# wk.net
KiCad netlist of a schematic drawn in Altium Designer
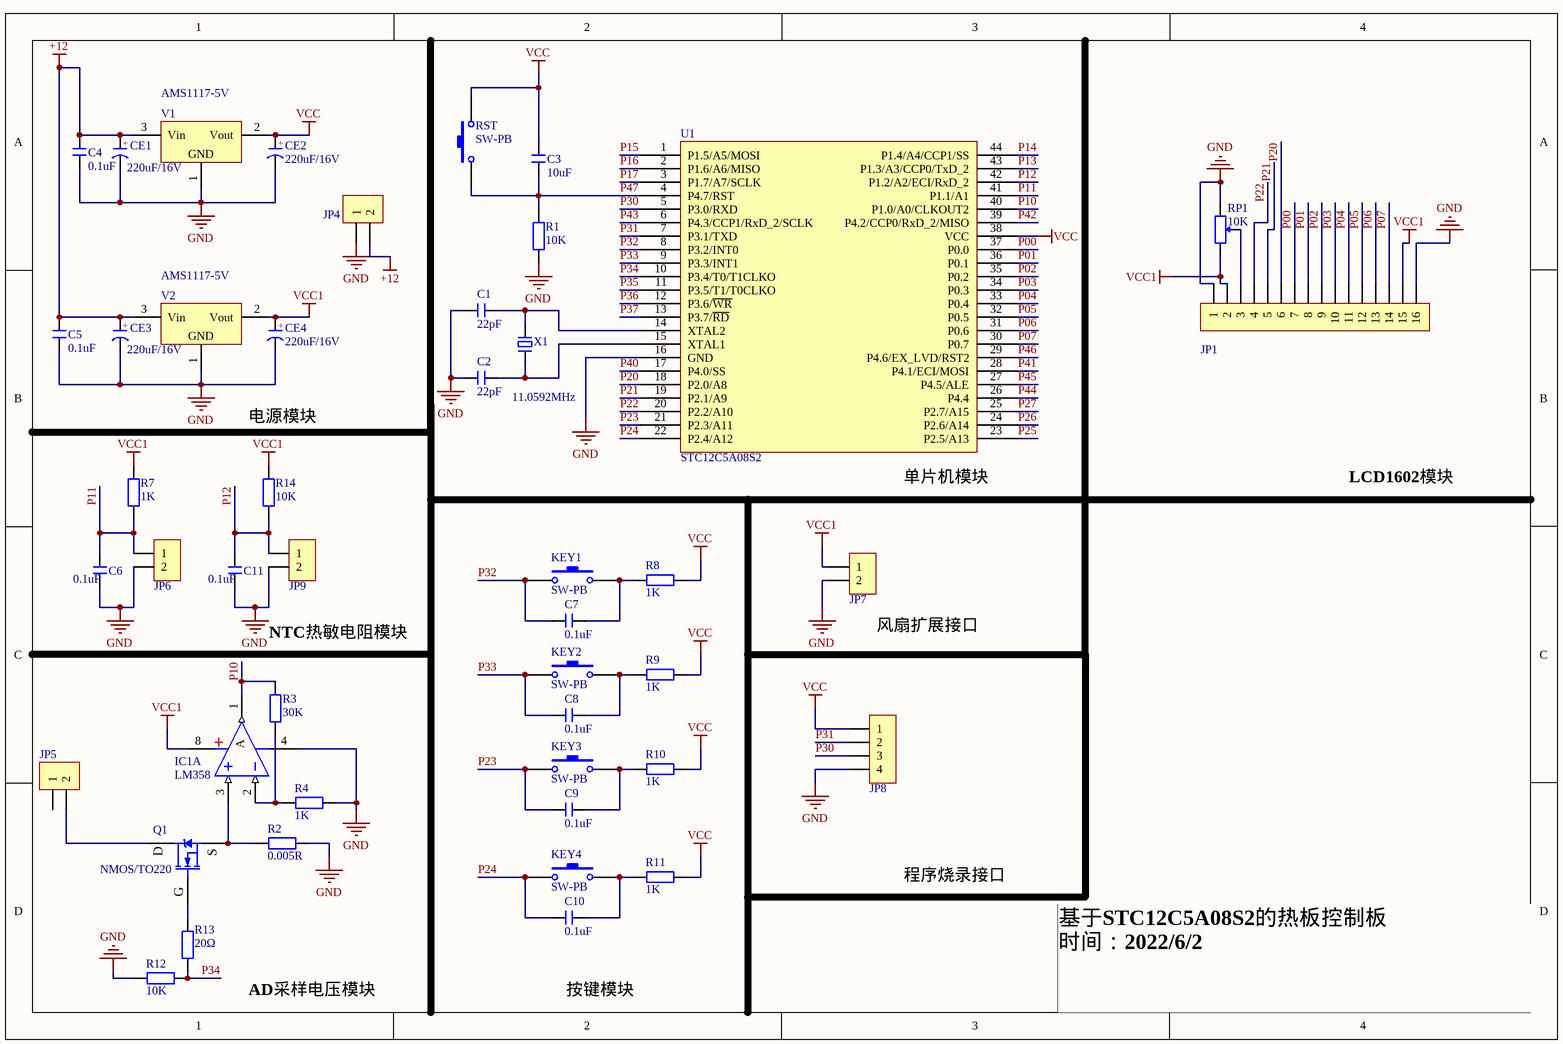
[diagram p0: wk.SchDoc]

(export (version "E")
  (design (tool "Eeschema 10.0.6"))
  (components
    (comp (ref "C1")
      (value "22pF")
      (footprint "C 0805_M")
      (description "贴片电容")
      (libsource (lib "0.1 - 电阻-电容-电感") (part "C"))
    )
    (comp (ref "C2")
      (value "22pF")
      (footprint "C 0805_M")
      (description "贴片电容")
      (libsource (lib "0.1 - 电阻-电容-电感") (part "C"))
    )
    (comp (ref "C3")
      (value "10uF")
      (footprint "C 0805_M")
      (description "贴片电容")
      (libsource (lib "0.1 - 电阻-电容-电感") (part "C"))
    )
    (comp (ref "C4")
      (value "0.1uF")
      (footprint "C 0805_M")
      (description "贴片电容")
      (libsource (lib "0.1 - 电阻-电容-电感") (part "C"))
    )
    (comp (ref "C5")
      (value "0.1uF")
      (footprint "C 0805_M")
      (description "贴片电容")
      (libsource (lib "0.1 - 电阻-电容-电感") (part "C"))
    )
    (comp (ref "C6")
      (value "0.1uF")
      (footprint "C 0805_M")
      (description "贴片电容")
      (libsource (lib "0.1 - 电阻-电容-电感") (part "C"))
    )
    (comp (ref "C7")
      (value "0.1uF")
      (footprint "C 0805_M")
      (description "贴片电容")
      (libsource (lib "0.1 - 电阻-电容-电感") (part "C"))
    )
    (comp (ref "C8")
      (value "0.1uF")
      (footprint "C 0805_M")
      (description "贴片电容")
      (libsource (lib "0.1 - 电阻-电容-电感") (part "C"))
    )
    (comp (ref "C9")
      (value "0.1uF")
      (footprint "C 0805_M")
      (description "贴片电容")
      (libsource (lib "0.1 - 电阻-电容-电感") (part "C"))
    )
    (comp (ref "C10")
      (value "0.1uF")
      (footprint "C 0805_M")
      (description "贴片电容")
      (libsource (lib "0.1 - 电阻-电容-电感") (part "C"))
    )
    (comp (ref "C11")
      (value "0.1uF")
      (footprint "C 0805_M")
      (description "贴片电容")
      (libsource (lib "0.1 - 电阻-电容-电感") (part "C"))
    )
    (comp (ref "CE1")
      (value "220uF/16V")
      (footprint "CAP 2.5*6.3*7")
      (description "直插电解电容")
      (libsource (lib "0.1 - 电阻-电容-电感") (part "CE"))
    )
    (comp (ref "CE2")
      (value "220uF/16V")
      (footprint "CAP 2.5*6.3*7")
      (description "直插电解电容")
      (libsource (lib "0.1 - 电阻-电容-电感") (part "CE"))
    )
    (comp (ref "CE3")
      (value "220uF/16V")
      (footprint "CAP 2.5*6.3*7")
      (description "直插电解电容")
      (libsource (lib "0.1 - 电阻-电容-电感") (part "CE"))
    )
    (comp (ref "CE4")
      (value "220uF/16V")
      (footprint "CAP 2.5*6.3*7")
      (description "直插电解电容")
      (libsource (lib "0.1 - 电阻-电容-电感") (part "CE"))
    )
    (comp (ref "IC1")
      (value "LM358")
      (footprint "DIP8-300")
      (description "双路运放")
      (fields (field (name "版权归属") "源创客"))
      (libsource (lib "1.0 - 常见芯片") (part "LM358"))
    )
    (comp (ref "JP1")
      (value "HDR-1X16")
      (footprint "HDR2.54-LI-16P")
      (description "16P接插件")
      (fields (field (name "版权归属") "源创客"))
      (libsource (lib "4.5   - 接插件-脚距2.54") (part "Header 16"))
    )
    (comp (ref "JP4")
      (value "HDR-1X2")
      (footprint "KF2EDGK5.08-LI-2P")
      (description "2P接插件")
      (fields (field (name "版权归属") "源创客"))
      (libsource (lib "4.10 - 接插件-脚距5.08") (part "Header 2"))
    )
    (comp (ref "JP5")
      (value "HDR-1X2")
      (footprint "KF2EDGK5.08-LI-2P")
      (description "2P接插件")
      (fields (field (name "版权归属") "源创客"))
      (libsource (lib "4.10 - 接插件-脚距5.08") (part "Header 2"))
    )
    (comp (ref "JP6")
      (value "HDR-1X2")
      (footprint "HDR2.54-LI-2P")
      (description "2P接插件")
      (fields (field (name "版权归属") "封装库来自淘宝 ID：黄晶宝石"))
      (libsource (lib "5.4 - 接插件-脚距2.54 (100mil) ") (part "Header 2"))
    )
    (comp (ref "JP7")
      (value "HDR-1X2")
      (footprint "HDR2.54-LI-2P")
      (description "2P接插件")
      (fields (field (name "版权归属") "封装库来自淘宝 ID：黄晶宝石"))
      (libsource (lib "5.4 - 接插件-脚距2.54 (100mil) ") (part "Header 2"))
    )
    (comp (ref "JP8")
      (value "HDR-1X4")
      (footprint "HDR2.54-LI-4P")
      (description "4P接插件")
      (fields (field (name "版权归属") "封装库来自淘宝 ID：黄晶宝石"))
      (libsource (lib "5.4 - 接插件-脚距2.54 (100mil) ") (part "Header 4"))
    )
    (comp (ref "JP9")
      (value "HDR-1X2")
      (footprint "HDR2.54-LI-2P")
      (description "2P接插件")
      (fields (field (name "版权归属") "封装库来自淘宝 ID：黄晶宝石"))
      (libsource (lib "5.4 - 接插件-脚距2.54 (100mil) ") (part "Header 2"))
    )
    (comp (ref "KEY1")
      (value "SW-PB")
      (footprint "SW_PB2_A1")
      (description "微动开关")
      (fields (field (name "PUBLISHER") "Altium Limited"))
      (libsource (lib "0.7 - 常用按键-开关") (part "SW-PB"))
    )
    (comp (ref "KEY2")
      (value "SW-PB")
      (footprint "SW_PB2_A1")
      (description "微动开关")
      (fields (field (name "PUBLISHER") "Altium Limited"))
      (libsource (lib "0.7 - 常用按键-开关") (part "SW-PB"))
    )
    (comp (ref "KEY3")
      (value "SW-PB")
      (footprint "SW_PB2_A1")
      (description "微动开关")
      (fields (field (name "PUBLISHER") "Altium Limited"))
      (libsource (lib "0.7 - 常用按键-开关") (part "SW-PB"))
    )
    (comp (ref "KEY4")
      (value "SW-PB")
      (footprint "SW_PB2_A1")
      (description "微动开关")
      (fields (field (name "PUBLISHER") "Altium Limited"))
      (libsource (lib "0.7 - 常用按键-开关") (part "SW-PB"))
    )
    (comp (ref "Q1")
      (value "NMOS/TO220")
      (footprint "TO220A")
      (description "N沟场效应管")
      (libsource (lib "0.5 - 场效应管-可控硅") (part "IRF840"))
    )
    (comp (ref "R1")
      (value "10K")
      (footprint "RS 1/8W")
      (description "色环电阻")
      (fields (field (name "版权归属") "封装库来自淘宝 ID：黄晶宝石"))
      (libsource (lib "0.1 - 电阻-电容-电感") (part "R-S"))
    )
    (comp (ref "R2")
      (value "0.005R")
      (footprint "RI 1.25W - 0.9mm")
      (description "电流检测电阻")
      (fields (field (name "版权归属") "源创客"))
      (libsource (lib "3.1   - 电阻-电容-电感") (part "R-I"))
    )
    (comp (ref "R3")
      (value "30K")
      (footprint "RS 1/8W")
      (description "色环电阻")
      (fields (field (name "版权归属") "封装库来自淘宝 ID：黄晶宝石"))
      (libsource (lib "0.1 - 电阻-电容-电感") (part "R-S"))
    )
    (comp (ref "R4")
      (value "1K")
      (footprint "RS 1/8W")
      (description "色环电阻")
      (fields (field (name "版权归属") "封装库来自淘宝 ID：黄晶宝石"))
      (libsource (lib "0.1 - 电阻-电容-电感") (part "R-S"))
    )
    (comp (ref "R7")
      (value "1K")
      (footprint "RS 1/8W")
      (description "色环电阻")
      (fields (field (name "版权归属") "封装库来自淘宝 ID：黄晶宝石"))
      (libsource (lib "0.1 - 电阻-电容-电感") (part "R-S"))
    )
    (comp (ref "R8")
      (value "1K")
      (footprint "RS 1/8W")
      (description "色环电阻")
      (fields (field (name "版权归属") "封装库来自淘宝 ID：黄晶宝石"))
      (libsource (lib "0.1 - 电阻-电容-电感") (part "R-S"))
    )
    (comp (ref "R9")
      (value "1K")
      (footprint "RS 1/8W")
      (description "色环电阻")
      (fields (field (name "版权归属") "封装库来自淘宝 ID：黄晶宝石"))
      (libsource (lib "0.1 - 电阻-电容-电感") (part "R-S"))
    )
    (comp (ref "R10")
      (value "1K")
      (footprint "RS 1/8W")
      (description "色环电阻")
      (fields (field (name "版权归属") "封装库来自淘宝 ID：黄晶宝石"))
      (libsource (lib "0.1 - 电阻-电容-电感") (part "R-S"))
    )
    (comp (ref "R11")
      (value "1K")
      (footprint "RS 1/8W")
      (description "色环电阻")
      (fields (field (name "版权归属") "封装库来自淘宝 ID：黄晶宝石"))
      (libsource (lib "0.1 - 电阻-电容-电感") (part "R-S"))
    )
    (comp (ref "R12")
      (value "10K")
      (footprint "RS 1/8W")
      (description "色环电阻")
      (fields (field (name "版权归属") "封装库来自淘宝 ID：黄晶宝石"))
      (libsource (lib "0.1 - 电阻-电容-电感") (part "R-S"))
    )
    (comp (ref "R13")
      (value "20Ω")
      (footprint "RS 1/8W")
      (description "色环电阻")
      (fields (field (name "版权归属") "封装库来自淘宝 ID：黄晶宝石"))
      (libsource (lib "0.1 - 电阻-电容-电感") (part "R-S"))
    )
    (comp (ref "R14")
      (value "10K")
      (footprint "RS 1/8W")
      (description "色环电阻")
      (fields (field (name "版权归属") "封装库来自淘宝 ID：黄晶宝石"))
      (libsource (lib "0.1 - 电阻-电容-电感") (part "R-S"))
    )
    (comp (ref "RP1")
      (value "10K")
      (footprint "3362P")
      (description "单联电位器")
      (fields (field (name "版权归属") "封装库来自淘宝 ID：黄晶宝石"))
      (libsource (lib "0.1 - 电阻-电容-电感") (part "RP"))
    )
    (comp (ref "RST")
      (value "SW-PB")
      (footprint "SW_PB2_A1")
      (description "微动开关")
      (fields (field (name "PUBLISHER") "Altium Limited"))
      (libsource (lib "0.7 - 常用按键-开关") (part "SW-PB"))
    )
    (comp (ref "U1")
      (value "STC12C5A08S2")
      (footprint "LQFP44 10x10_L")
      (description "STC单片机")
      (fields (field (name "版权归属") "封装库来自淘宝卖家 ID：黄晶宝石"))
      (libsource (lib "2.8 - STC系列单片机") (part "STC12C5AxxS2-44pin"))
    )
    (comp (ref "V1")
      (value "AMS1117-5V")
      (footprint "SOT223_L")
      (description "三端稳压芯片")
      (libsource (lib "1.1 - 电源类芯片") (part "AMS1117"))
    )
    (comp (ref "V2")
      (value "AMS1117-5V")
      (footprint "SOT223_L")
      (description "三端稳压芯片")
      (libsource (lib "1.1 - 电源类芯片") (part "AMS1117"))
    )
    (comp (ref "X1")
      (value "11.0592MHz")
      (footprint "OSC 5032-2P")
      (description "2脚无源脚晶振")
      (fields (field (name "版权归属") "封装库来自淘宝卖家 ID：黄晶宝石"))
      (libsource (lib "2.0 - 保险丝-晶振-光耦") (part "XTAL-2P"))
    )
  )
  (nets
    (net (code "1") (name "+12") (class "Default")
      (node (ref "C4") (pin "2") (pinfunction "2_2") (pintype "passive"))
      (node (ref "C5") (pin "2") (pinfunction "2_2") (pintype "passive"))
      (node (ref "CE1") (pin "1") (pinfunction "A_1") (pintype "passive"))
      (node (ref "CE3") (pin "1") (pinfunction "A_1") (pintype "passive"))
      (node (ref "JP4") (pin "2") (pinfunction "2_2") (pintype "passive"))
      (node (ref "V1") (pin "3") (pinfunction "Vin_3") (pintype "passive"))
      (node (ref "V2") (pin "3") (pinfunction "Vin_3") (pintype "passive"))
    )
    (net (code "2") (name "/P00") (class "Default")
      (node (ref "JP1") (pin "7") (pinfunction "7_7") (pintype "passive"))
      (node (ref "U1") (pin "37") (pinfunction "P0.0_37") (pintype "passive"))
    )
    (net (code "3") (name "/P01") (class "Default")
      (node (ref "JP1") (pin "8") (pinfunction "8_8") (pintype "passive"))
      (node (ref "U1") (pin "36") (pinfunction "P0.1_36") (pintype "passive"))
    )
    (net (code "4") (name "/P02") (class "Default")
      (node (ref "JP1") (pin "9") (pinfunction "9_9") (pintype "passive"))
      (node (ref "U1") (pin "35") (pinfunction "P0.2_35") (pintype "passive"))
    )
    (net (code "5") (name "/P03") (class "Default")
      (node (ref "JP1") (pin "10") (pinfunction "10_10") (pintype "passive"))
      (node (ref "U1") (pin "34") (pinfunction "P0.3_34") (pintype "passive"))
    )
    (net (code "6") (name "/P04") (class "Default")
      (node (ref "JP1") (pin "11") (pinfunction "11_11") (pintype "passive"))
      (node (ref "U1") (pin "33") (pinfunction "P0.4_33") (pintype "passive"))
    )
    (net (code "7") (name "/P05") (class "Default")
      (node (ref "JP1") (pin "12") (pinfunction "12_12") (pintype "passive"))
      (node (ref "U1") (pin "32") (pinfunction "P0.5_32") (pintype "passive"))
    )
    (net (code "8") (name "/P06") (class "Default")
      (node (ref "JP1") (pin "13") (pinfunction "13_13") (pintype "passive"))
      (node (ref "U1") (pin "31") (pinfunction "P0.6_31") (pintype "passive"))
    )
    (net (code "9") (name "/P07") (class "Default")
      (node (ref "JP1") (pin "14") (pinfunction "14_14") (pintype "passive"))
      (node (ref "U1") (pin "30") (pinfunction "P0.7_30") (pintype "passive"))
    )
    (net (code "10") (name "/P10") (class "Default")
      (node (ref "IC1") (pin "1") (pinfunction "OUT_1") (pintype "output"))
      (node (ref "R3") (pin "1") (pinfunction "1_1") (pintype "passive"))
      (node (ref "U1") (pin "40") (pinfunction "P1.0/A0/CLKOUT2_40") (pintype "passive"))
    )
    (net (code "11") (name "/P11") (class "Default")
      (node (ref "C6") (pin "2") (pinfunction "2_2") (pintype "passive"))
      (node (ref "JP6") (pin "1") (pinfunction "1_1") (pintype "passive"))
      (node (ref "R7") (pin "1") (pinfunction "1_1") (pintype "passive"))
      (node (ref "U1") (pin "41") (pinfunction "P1.1/A1_41") (pintype "passive"))
    )
    (net (code "12") (name "/P12") (class "Default")
      (node (ref "C11") (pin "2") (pinfunction "2_2") (pintype "passive"))
      (node (ref "JP9") (pin "1") (pinfunction "1_1") (pintype "passive"))
      (node (ref "R14") (pin "1") (pinfunction "1_1") (pintype "passive"))
      (node (ref "U1") (pin "42") (pinfunction "P1.2/A2/ECI/RxD_2_42") (pintype "passive"))
    )
    (net (code "13") (name "/P13") (class "Default")
      (node (ref "U1") (pin "43") (pinfunction "P1.3/A3/CCP0/TxD_2_43") (pintype "passive"))
    )
    (net (code "14") (name "/P14") (class "Default")
      (node (ref "U1") (pin "44") (pinfunction "P1.4/A4/CCP1/SS_44") (pintype "passive"))
    )
    (net (code "15") (name "/P15") (class "Default")
      (node (ref "U1") (pin "1") (pinfunction "P1.5/A5/MOSI_1") (pintype "passive"))
    )
    (net (code "16") (name "/P16") (class "Default")
      (node (ref "U1") (pin "2") (pinfunction "P1.6/A6/MISO_2") (pintype "passive"))
    )
    (net (code "17") (name "/P17") (class "Default")
      (node (ref "U1") (pin "3") (pinfunction "P1.7/A7/SCLK_3") (pintype "passive"))
    )
    (net (code "18") (name "/P20") (class "Default")
      (node (ref "JP1") (pin "6") (pinfunction "6_6") (pintype "passive"))
      (node (ref "U1") (pin "18") (pinfunction "P2.0/A8_18") (pintype "passive"))
    )
    (net (code "19") (name "/P21") (class "Default")
      (node (ref "JP1") (pin "5") (pinfunction "5_5") (pintype "passive"))
      (node (ref "U1") (pin "19") (pinfunction "P2.1/A9_19") (pintype "passive"))
    )
    (net (code "20") (name "/P22") (class "Default")
      (node (ref "JP1") (pin "4") (pinfunction "4_4") (pintype "passive"))
      (node (ref "U1") (pin "20") (pinfunction "P2.2/A10_20") (pintype "passive"))
    )
    (net (code "21") (name "/P23") (class "Default")
      (node (ref "C9") (pin "2") (pinfunction "2_2") (pintype "passive"))
      (node (ref "KEY3") (pin "1") (pinfunction "1_1") (pintype "passive"))
      (node (ref "U1") (pin "21") (pinfunction "P2.3/A11_21") (pintype "passive"))
    )
    (net (code "22") (name "/P24") (class "Default")
      (node (ref "C10") (pin "2") (pinfunction "2_2") (pintype "passive"))
      (node (ref "KEY4") (pin "1") (pinfunction "1_1") (pintype "passive"))
      (node (ref "U1") (pin "22") (pinfunction "P2.4/A12_22") (pintype "passive"))
    )
    (net (code "23") (name "/P25") (class "Default")
      (node (ref "U1") (pin "23") (pinfunction "P2.5/A13_23") (pintype "passive"))
    )
    (net (code "24") (name "/P26") (class "Default")
      (node (ref "U1") (pin "24") (pinfunction "P2.6/A14_24") (pintype "passive"))
    )
    (net (code "25") (name "/P27") (class "Default")
      (node (ref "U1") (pin "25") (pinfunction "P2.7/A15_25") (pintype "passive"))
    )
    (net (code "26") (name "/P30") (class "Default")
      (node (ref "JP8") (pin "3") (pinfunction "3_3") (pintype "passive"))
      (node (ref "U1") (pin "5") (pinfunction "P3.0/RXD_5") (pintype "passive"))
    )
    (net (code "27") (name "/P31") (class "Default")
      (node (ref "JP8") (pin "2") (pinfunction "2_2") (pintype "passive"))
      (node (ref "U1") (pin "7") (pinfunction "P3.1/TXD_7") (pintype "passive"))
    )
    (net (code "28") (name "/P32") (class "Default")
      (node (ref "C7") (pin "2") (pinfunction "2_2") (pintype "passive"))
      (node (ref "KEY1") (pin "1") (pinfunction "1_1") (pintype "passive"))
      (node (ref "U1") (pin "8") (pinfunction "P3.2/INT0_8") (pintype "passive"))
    )
    (net (code "29") (name "/P33") (class "Default")
      (node (ref "C8") (pin "2") (pinfunction "2_2") (pintype "passive"))
      (node (ref "KEY2") (pin "1") (pinfunction "1_1") (pintype "passive"))
      (node (ref "U1") (pin "9") (pinfunction "P3.3/INT1_9") (pintype "passive"))
    )
    (net (code "30") (name "/P34") (class "Default")
      (node (ref "R12") (pin "1") (pinfunction "1_1") (pintype "passive"))
      (node (ref "R13") (pin "2") (pinfunction "2_2") (pintype "passive"))
      (node (ref "U1") (pin "10") (pinfunction "P3.4/T0/T1CLKO_10") (pintype "passive"))
    )
    (net (code "31") (name "/P35") (class "Default")
      (node (ref "U1") (pin "11") (pinfunction "P3.5/T1/T0CLKO_11") (pintype "passive"))
    )
    (net (code "32") (name "/P36") (class "Default")
      (node (ref "U1") (pin "12") (pinfunction "P3.6/~{WR}_12") (pintype "passive"))
    )
    (net (code "33") (name "/P37") (class "Default")
      (node (ref "U1") (pin "13") (pinfunction "P3.7/~{RD}_13") (pintype "passive"))
    )
    (net (code "34") (name "/P40") (class "Default")
      (node (ref "U1") (pin "17") (pinfunction "P4.0/SS_17") (pintype "passive"))
    )
    (net (code "35") (name "/P41") (class "Default")
      (node (ref "U1") (pin "28") (pinfunction "P4.1/ECI/MOSI_28") (pintype "passive"))
    )
    (net (code "36") (name "/P42") (class "Default")
      (node (ref "U1") (pin "39") (pinfunction "P4.2/CCP0/RxD_2/MISO_39") (pintype "passive"))
    )
    (net (code "37") (name "/P43") (class "Default")
      (node (ref "U1") (pin "6") (pinfunction "P4.3/CCP1/RxD_2/SCLK_6") (pintype "passive"))
    )
    (net (code "38") (name "/P44") (class "Default")
      (node (ref "U1") (pin "26") (pinfunction "P4.4_26") (pintype "passive"))
    )
    (net (code "39") (name "/P45") (class "Default")
      (node (ref "U1") (pin "27") (pinfunction "P4.5/ALE_27") (pintype "passive"))
    )
    (net (code "40") (name "/P46") (class "Default")
      (node (ref "U1") (pin "29") (pinfunction "P4.6/EX_LVD/RST2_29") (pintype "passive"))
    )
    (net (code "41") (name "/P47") (class "Default")
      (node (ref "C3") (pin "1") (pinfunction "1_1") (pintype "passive"))
      (node (ref "R1") (pin "2") (pinfunction "2_2") (pintype "passive"))
      (node (ref "RST") (pin "1") (pinfunction "1_1") (pintype "passive"))
      (node (ref "U1") (pin "4") (pinfunction "P4.7/RST_4") (pintype "passive"))
    )
    (net (code "42") (name "GND") (class "Default")
      (node (ref "C1") (pin "2") (pinfunction "2_2") (pintype "passive"))
      (node (ref "C11") (pin "1") (pinfunction "1_1") (pintype "passive"))
      (node (ref "C2") (pin "2") (pinfunction "2_2") (pintype "passive"))
      (node (ref "C4") (pin "1") (pinfunction "1_1") (pintype "passive"))
      (node (ref "C5") (pin "1") (pinfunction "1_1") (pintype "passive"))
      (node (ref "C6") (pin "1") (pinfunction "1_1") (pintype "passive"))
      (node (ref "CE1") (pin "2") (pinfunction "K_2") (pintype "passive"))
      (node (ref "CE2") (pin "2") (pinfunction "K_2") (pintype "passive"))
      (node (ref "CE3") (pin "2") (pinfunction "K_2") (pintype "passive"))
      (node (ref "CE4") (pin "2") (pinfunction "K_2") (pintype "passive"))
      (node (ref "IC1") (pin "4") (pinfunction "V-_4") (pintype "power_in"))
      (node (ref "JP1") (pin "1") (pinfunction "1_1") (pintype "passive"))
      (node (ref "JP1") (pin "16") (pinfunction "16_16") (pintype "passive"))
      (node (ref "JP4") (pin "1") (pinfunction "1_1") (pintype "passive"))
      (node (ref "JP6") (pin "2") (pinfunction "2_2") (pintype "passive"))
      (node (ref "JP7") (pin "2") (pinfunction "2_2") (pintype "passive"))
      (node (ref "JP8") (pin "4") (pinfunction "4_4") (pintype "passive"))
      (node (ref "JP9") (pin "2") (pinfunction "2_2") (pintype "passive"))
      (node (ref "R1") (pin "1") (pinfunction "1_1") (pintype "passive"))
      (node (ref "R12") (pin "2") (pinfunction "2_2") (pintype "passive"))
      (node (ref "R2") (pin "2") (pinfunction "2_2") (pintype "passive"))
      (node (ref "R4") (pin "2") (pinfunction "2_2") (pintype "passive"))
      (node (ref "RP1") (pin "1") (pinfunction "1_1") (pintype "passive"))
      (node (ref "U1") (pin "16") (pinfunction "GND_16") (pintype "passive"))
      (node (ref "V1") (pin "1") (pinfunction "GND_1") (pintype "passive"))
      (node (ref "V2") (pin "1") (pinfunction "GND_1") (pintype "passive"))
    )
    (net (code "43") (name "Net-(C7-Pad1)") (class "Default")
      (node (ref "C7") (pin "1") (pinfunction "1_1") (pintype "passive"))
      (node (ref "KEY1") (pin "2") (pinfunction "2_2") (pintype "passive"))
      (node (ref "R8") (pin "2") (pinfunction "2_2") (pintype "passive"))
    )
    (net (code "44") (name "Net-(C8-Pad1)") (class "Default")
      (node (ref "C8") (pin "1") (pinfunction "1_1") (pintype "passive"))
      (node (ref "KEY2") (pin "2") (pinfunction "2_2") (pintype "passive"))
      (node (ref "R9") (pin "2") (pinfunction "2_2") (pintype "passive"))
    )
    (net (code "45") (name "Net-(C9-Pad1)") (class "Default")
      (node (ref "C9") (pin "1") (pinfunction "1_1") (pintype "passive"))
      (node (ref "KEY3") (pin "2") (pinfunction "2_2") (pintype "passive"))
      (node (ref "R10") (pin "2") (pinfunction "2_2") (pintype "passive"))
    )
    (net (code "46") (name "Net-(C10-Pad1)") (class "Default")
      (node (ref "C10") (pin "1") (pinfunction "1_1") (pintype "passive"))
      (node (ref "KEY4") (pin "2") (pinfunction "2_2") (pintype "passive"))
      (node (ref "R11") (pin "2") (pinfunction "2_2") (pintype "passive"))
    )
    (net (code "47") (name "Net-(IC1A-IN+)") (class "Default")
      (node (ref "IC1") (pin "3") (pinfunction "IN+_3") (pintype "input"))
      (node (ref "Q1") (pin "3") (pinfunction "S_3") (pintype "passive"))
      (node (ref "R2") (pin "1") (pinfunction "1_1") (pintype "passive"))
    )
    (net (code "48") (name "Net-(IC1A-IN-)") (class "Default")
      (node (ref "IC1") (pin "2") (pinfunction "IN-_2") (pintype "input"))
      (node (ref "R3") (pin "2") (pinfunction "2_2") (pintype "passive"))
      (node (ref "R4") (pin "1") (pinfunction "1_1") (pintype "passive"))
    )
    (net (code "49") (name "Net-(JP1-Pad3)") (class "Default")
      (node (ref "JP1") (pin "3") (pinfunction "3_3") (pintype "passive"))
      (node (ref "RP1") (pin "2") (pinfunction "2_2") (pintype "passive"))
    )
    (net (code "50") (name "Net-(Q1-D)") (class "Default")
      (node (ref "JP5") (pin "2") (pinfunction "2_2") (pintype "passive"))
      (node (ref "Q1") (pin "2") (pinfunction "D_2") (pintype "passive"))
    )
    (net (code "51") (name "Net-(Q1-G)") (class "Default")
      (node (ref "Q1") (pin "1") (pinfunction "G_1") (pintype "passive"))
      (node (ref "R13") (pin "1") (pinfunction "1_1") (pintype "passive"))
    )
    (net (code "52") (name "Net-(U1-XTAL1)") (class "Default")
      (node (ref "C2") (pin "1") (pinfunction "1_1") (pintype "passive"))
      (node (ref "U1") (pin "15") (pinfunction "XTAL1_15") (pintype "passive"))
      (node (ref "X1") (pin "1") (pinfunction "1_1") (pintype "passive"))
    )
    (net (code "53") (name "Net-(U1-XTAL2)") (class "Default")
      (node (ref "C1") (pin "1") (pinfunction "1_1") (pintype "passive"))
      (node (ref "U1") (pin "14") (pinfunction "XTAL2_14") (pintype "passive"))
      (node (ref "X1") (pin "2") (pinfunction "2_2") (pintype "passive"))
    )
    (net (code "54") (name "VCC") (class "Default")
      (node (ref "C3") (pin "2") (pinfunction "2_2") (pintype "passive"))
      (node (ref "CE2") (pin "1") (pinfunction "A_1") (pintype "passive"))
      (node (ref "JP8") (pin "1") (pinfunction "1_1") (pintype "passive"))
      (node (ref "R10") (pin "1") (pinfunction "1_1") (pintype "passive"))
      (node (ref "R11") (pin "1") (pinfunction "1_1") (pintype "passive"))
      (node (ref "R8") (pin "1") (pinfunction "1_1") (pintype "passive"))
      (node (ref "R9") (pin "1") (pinfunction "1_1") (pintype "passive"))
      (node (ref "RST") (pin "2") (pinfunction "2_2") (pintype "passive"))
      (node (ref "U1") (pin "38") (pinfunction "VCC_38") (pintype "passive"))
      (node (ref "V1") (pin "2") (pinfunction "Vout_2") (pintype "passive"))
    )
    (net (code "55") (name "VCC1") (class "Default")
      (node (ref "CE4") (pin "1") (pinfunction "A_1") (pintype "passive"))
      (node (ref "IC1") (pin "8") (pinfunction "V+_8") (pintype "power_in"))
      (node (ref "JP1") (pin "15") (pinfunction "15_15") (pintype "passive"))
      (node (ref "JP1") (pin "2") (pinfunction "2_2") (pintype "passive"))
      (node (ref "JP7") (pin "1") (pinfunction "1_1") (pintype "passive"))
      (node (ref "R14") (pin "2") (pinfunction "2_2") (pintype "passive"))
      (node (ref "R7") (pin "2") (pinfunction "2_2") (pintype "passive"))
      (node (ref "RP1") (pin "3") (pinfunction "3_3") (pintype "passive"))
      (node (ref "V2") (pin "2") (pinfunction "Vout_2") (pintype "passive"))
    )
    (net (code "56") (name "unconnected-(JP5-Pad1)") (class "Default")
      (node (ref "JP5") (pin "1") (pinfunction "1_1") (pintype "passive"))
    )
  )
)
